# LED_INDICATOR.net
KiCad netlist of a schematic drawn in Altium Designer
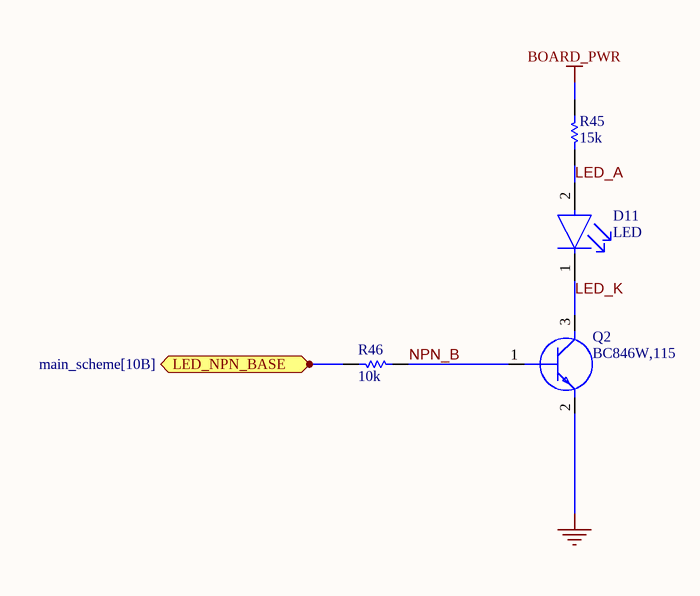
[diagram p0: LED_INDICATOR.SchDoc]

(export (version "E")
  (design (tool "Eeschema 10.0.6"))
  (components
    (comp (ref "D11")
      (value "LED")
      (footprint "PcbLib1:0603_RED_LED")
      (description "LED RED DIFFUSED 1608 SMD")
      (fields
        (field (name "MANUFACTURER") "Rohm")
        (field (name "OCTOPART") "https://octopart.com/sml-d12u1wt86-rohm-70850259")
      )
      (libsource (lib "Schlib1") (part "0603_RED_LED_2V2"))
    )
    (comp (ref "Q2")
      (value "BC846W,115")
      (footprint "SamacSys:SOT65P210X110-3N")
      (description "Transistor BJT NPN")
      (fields (field (name "MOUSER PART NUMBER") "771-BC846W115"))
      (libsource (lib "*") (part "BC846W,115"))
    )
    (comp (ref "R45")
      (value "15k")
      (footprint "PcbLib1:RESC1005X40X25NL05T05")
      (fields (field (name "PART NUMBER") "ERJ2RKF6800X") (field (name "MANUFACTURER") "Panasonic"))
      (libsource (lib "Schlib1") (part "Resistor 0402 100mW"))
    )
    (comp (ref "R46")
      (value "10k")
      (footprint "PcbLib1:RESC1005X40X25NL05T05")
      (fields (field (name "PART NUMBER") "ERJ2RKF6800X") (field (name "MANUFACTURER") "Panasonic"))
      (libsource (lib "Schlib1") (part "Resistor 0402 100mW"))
    )
  )
  (nets
    (net (code "1") (name "/LED_A") (class "Default")
      (node (ref "D11") (pin "2") (pinfunction "A_2") (pintype "passive"))
      (node (ref "R45") (pin "1") (pinfunction "1_1") (pintype "passive"))
    )
    (net (code "2") (name "/LED_K") (class "Default")
      (node (ref "D11") (pin "1") (pinfunction "C_1") (pintype "passive"))
      (node (ref "Q2") (pin "3") (pinfunction "C_3") (pintype "passive"))
    )
    (net (code "3") (name "/LED_NPN_BASE") (class "Default")
      (node (ref "R46") (pin "2") (pinfunction "2_2") (pintype "passive"))
    )
    (net (code "4") (name "/NPN_B") (class "Default")
      (node (ref "Q2") (pin "1") (pinfunction "B_1") (pintype "passive"))
      (node (ref "R46") (pin "1") (pinfunction "1_1") (pintype "passive"))
    )
    (net (code "5") (name "BOARD_PWR") (class "Default")
      (node (ref "R45") (pin "2") (pinfunction "2_2") (pintype "passive"))
    )
    (net (code "6") (name "GND") (class "Default")
      (node (ref "Q2") (pin "2") (pinfunction "E_2") (pintype "passive"))
    )
  )
)
